# 24-UltrasonicSensors.net
KiCad netlist of a schematic drawn in Altium Designer
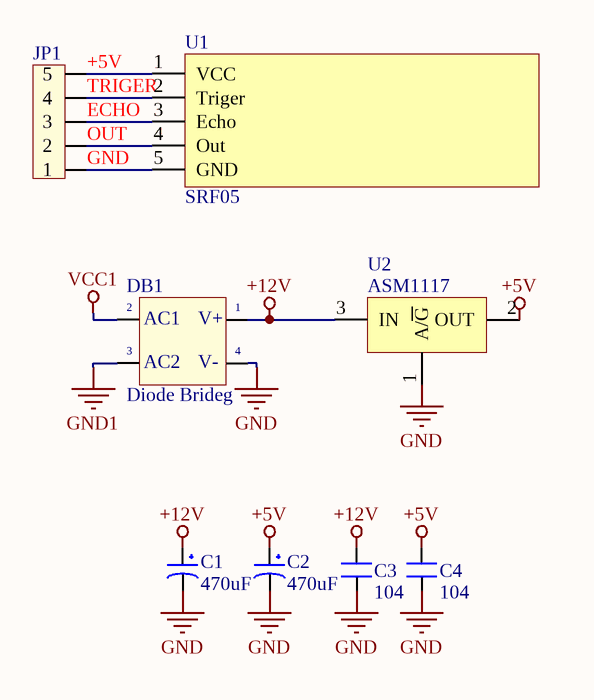
[diagram p0: 24-UltrasonicSensors (SRF05).SchDoc]

(export (version "E")
  (design (tool "Eeschema 10.0.6"))
  (components
    (comp (ref "C1")
      (value "470uF")
      (footprint "C-ALU-D6.5")
      (description "Cap P  0,1uF < 22uF , 16 - 50V")
      (libsource (lib "PART") (part "CP1"))
    )
    (comp (ref "C2")
      (value "470uF")
      (footprint "C-ALU-D6.5")
      (description "Cap P  0,1uF < 22uF , 16 - 50V")
      (libsource (lib "PART") (part "CP1"))
    )
    (comp (ref "C3")
      (value "104")
      (footprint "C-0805")
      (fields (field (name "DESIGNED BY") "VanDungEvn"))
      (libsource (lib "syhaunguyen") (part "CN"))
    )
    (comp (ref "C4")
      (value "104")
      (footprint "C-0805")
      (fields (field (name "DESIGNED BY") "VanDungEvn"))
      (libsource (lib "syhaunguyen") (part "CN"))
    )
    (comp (ref "DB1")
      (value "Diode Brideg")
      (footprint "D-DB-1A-SMD")
      (description "Convert AC to DC voltage, 4 pin")
      (libsource (lib "PART") (part "DB"))
    )
    (comp (ref "JP1") (value "JP5") (footprint "JP5") (libsource (lib "syhaunguyen") (part "JP5")))
    (comp (ref "U1") (value "SRF05") (libsource (lib "MrQuan") (part "SRF05")))
    (comp (ref "U2")
      (value "ASM1117")
      (footprint "TO-252")
      (libsource (lib "doAnTotNghiep2017Lib") (part "ASM1117"))
    )
  )
  (nets
    (net (code "1") (name "+5V") (class "Default")
      (node (ref "C2") (pin "1") (pinfunction "1_1") (pintype "passive"))
      (node (ref "C4") (pin "2") (pinfunction "2_2") (pintype "passive"))
      (node (ref "JP1") (pin "5") (pinfunction "5_5") (pintype "passive"))
      (node (ref "U1") (pin "1") (pinfunction "VCC_1") (pintype "passive"))
      (node (ref "U2") (pin "2") (pinfunction "OUT_2") (pintype "passive"))
    )
    (net (code "2") (name "+12V") (class "Default")
      (node (ref "C1") (pin "1") (pinfunction "1_1") (pintype "passive"))
      (node (ref "C3") (pin "2") (pinfunction "2_2") (pintype "passive"))
      (node (ref "DB1") (pin "3") (pinfunction "AC2_3") (pintype "passive"))
      (node (ref "U2") (pin "3") (pinfunction "IN_3") (pintype "passive"))
    )
    (net (code "3") (name "/ECHO") (class "Default")
      (node (ref "JP1") (pin "3") (pinfunction "3_3") (pintype "passive"))
      (node (ref "U1") (pin "3") (pinfunction "Echo_3") (pintype "passive"))
    )
    (net (code "4") (name "/OUT") (class "Default")
      (node (ref "JP1") (pin "2") (pinfunction "2_2") (pintype "passive"))
      (node (ref "U1") (pin "4") (pinfunction "Out_4") (pintype "passive"))
    )
    (net (code "5") (name "/TRIGER") (class "Default")
      (node (ref "JP1") (pin "4") (pinfunction "4_4") (pintype "passive"))
      (node (ref "U1") (pin "2") (pinfunction "Triger_2") (pintype "passive"))
    )
    (net (code "6") (name "GND") (class "Default")
      (node (ref "C1") (pin "2") (pinfunction "2_2") (pintype "passive"))
      (node (ref "C2") (pin "2") (pinfunction "2_2") (pintype "passive"))
      (node (ref "C3") (pin "1") (pinfunction "1_1") (pintype "passive"))
      (node (ref "C4") (pin "1") (pinfunction "1_1") (pintype "passive"))
      (node (ref "DB1") (pin "4") (pinfunction "-V_OUT_4") (pintype "passive"))
      (node (ref "JP1") (pin "1") (pinfunction "1_1") (pintype "passive"))
      (node (ref "U1") (pin "5") (pinfunction "GND_5") (pintype "passive"))
      (node (ref "U2") (pin "1") (pinfunction "A/~{G}_1") (pintype "passive"))
    )
    (net (code "7") (name "GND1") (class "Default")
      (node (ref "DB1") (pin "1") (pinfunction "+V_OUT_1") (pintype "passive"))
    )
    (net (code "8") (name "VCC1") (class "Default")
      (node (ref "DB1") (pin "2") (pinfunction "AC1_2") (pintype "passive"))
    )
  )
)
